# Sheet-circuit_de_puissance.net
KiCad netlist of a schematic drawn in Altium Designer
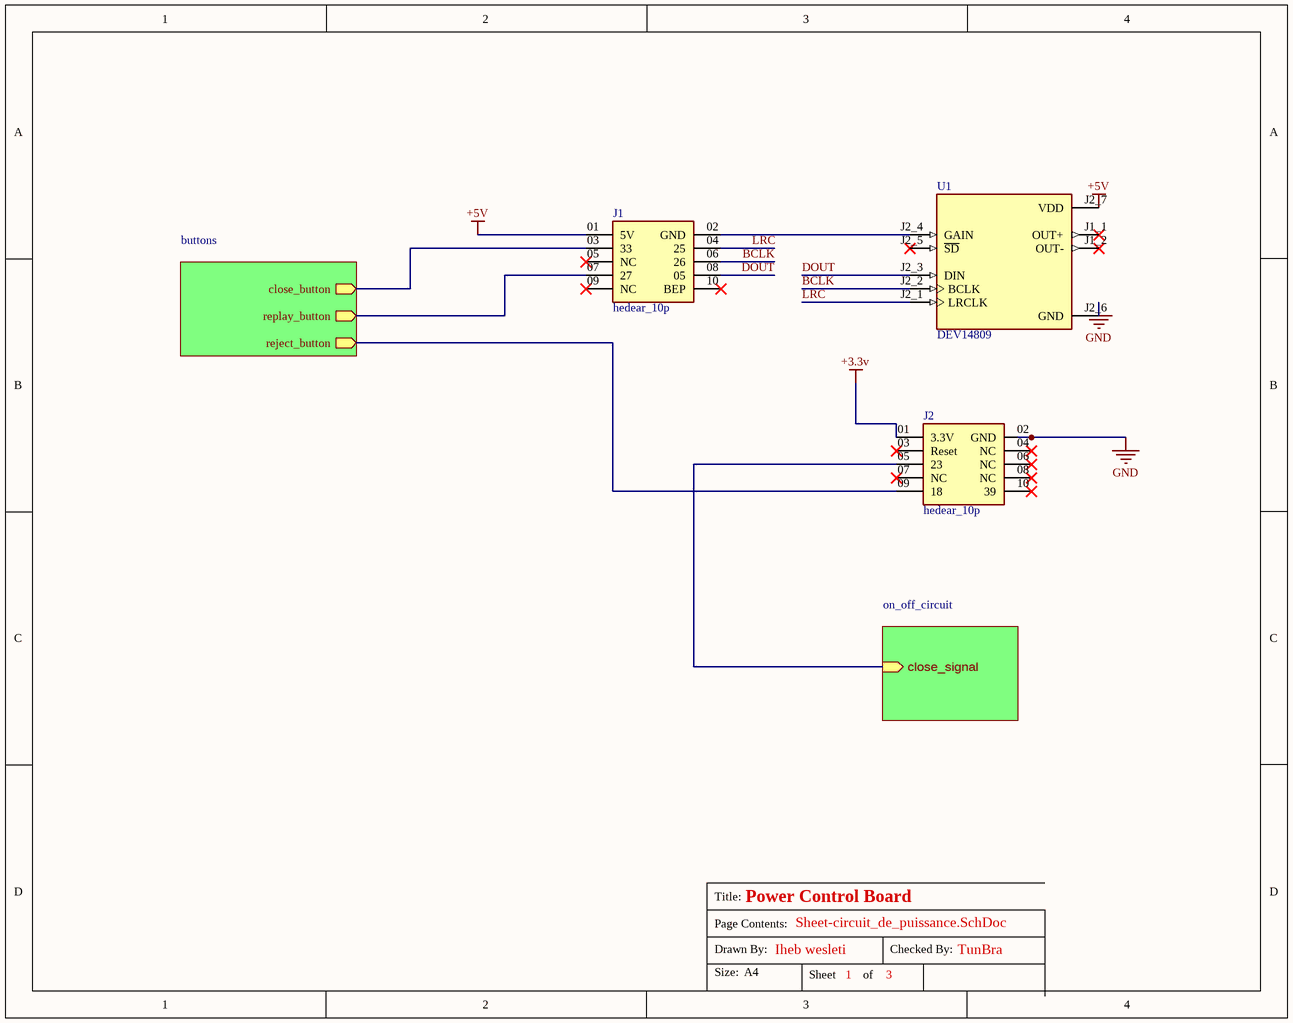
[diagram p0: Sheet-circuit_de_puissance.SchDoc]

(export (version "E")
  (design (tool "Eeschema 10.0.6"))
  (components
    (comp (ref "J1")
      (value "hedear_10p")
      (footprint "hedear10p")
      (fields (field (name "MP") "TSS-105-02-L-D"))
      (libsource (lib "Schlib_circuit_de_puissance") (part "hedear_10p"))
    )
    (comp (ref "J2")
      (value "hedear_10p")
      (footprint "hedear10p")
      (fields (field (name "MP") "TSS-105-02-L-D"))
      (libsource (lib "Schlib_circuit_de_puissance") (part "hedear_10p_1"))
    )
    (comp (ref "U1")
      (value "DEV14809")
      (footprint "MODULEson_DEV14809")
      (description "MAX98357A Audio Interface Audio - Platform Evaluation Expansion Board")
      (fields (field (name "MF") "Sparkfun Electronics"))
      (libsource (lib "Schlib_circuit_de_puissance") (part "DEV14809"))
    )
  )
  (nets
    (net (code "1") (name "+3.3v") (class "Default")
      (node (ref "J2") (pin "01") (pinfunction "3.3V_01") (pintype "passive"))
    )
    (net (code "2") (name "+5V") (class "Default")
      (node (ref "J1") (pin "01") (pinfunction "5V_01") (pintype "passive"))
      (node (ref "U1") (pin "J2_7") (pinfunction "VDD_J2_7") (pintype "power_in"))
    )
    (net (code "3") (name "/BCLK") (class "Default")
      (node (ref "J1") (pin "06") (pinfunction "26_06") (pintype "passive"))
      (node (ref "U1") (pin "J2_2") (pinfunction "BCLK_J2_2") (pintype "input"))
    )
    (net (code "4") (name "/DOUT") (class "Default")
      (node (ref "J1") (pin "08") (pinfunction "05_08") (pintype "passive"))
      (node (ref "U1") (pin "J2_3") (pinfunction "DIN_J2_3") (pintype "input"))
    )
    (net (code "5") (name "/LRC") (class "Default")
      (node (ref "J1") (pin "04") (pinfunction "25_04") (pintype "passive"))
      (node (ref "U1") (pin "J2_1") (pinfunction "LRCLK_J2_1") (pintype "input"))
    )
    (net (code "6") (name "/close_button") (class "Default")
      (node (ref "J1") (pin "03") (pinfunction "33_03") (pintype "passive"))
    )
    (net (code "7") (name "/close_signal") (class "Default")
      (node (ref "J2") (pin "05") (pinfunction "23_05") (pintype "passive"))
    )
    (net (code "8") (name "/reject_button") (class "Default")
      (node (ref "J2") (pin "09") (pinfunction "18_09") (pintype "passive"))
    )
    (net (code "9") (name "/replay_button") (class "Default")
      (node (ref "J1") (pin "07") (pinfunction "27_07") (pintype "passive"))
    )
    (net (code "10") (name "GND") (class "Default")
      (node (ref "J2") (pin "02") (pinfunction "GND_02") (pintype "passive"))
      (node (ref "U1") (pin "J2_6") (pinfunction "GND_J2_6") (pintype "power_in"))
    )
    (net (code "11") (name "Net-(J1-GND)") (class "Default")
      (node (ref "J1") (pin "02") (pinfunction "GND_02") (pintype "passive"))
      (node (ref "U1") (pin "J2_4") (pinfunction "GAIN_J2_4") (pintype "input"))
    )
    (net (code "12") (name "unconnected-(J1-BEP-Pad10)") (class "Default")
      (node (ref "J1") (pin "10") (pinfunction "BEP_10") (pintype "passive+no_connect"))
    )
    (net (code "13") (name "unconnected-(J1-NC-Pad05)") (class "Default")
      (node (ref "J1") (pin "05") (pinfunction "NC_05") (pintype "passive+no_connect"))
    )
    (net (code "14") (name "unconnected-(J1-NC-Pad09)") (class "Default")
      (node (ref "J1") (pin "09") (pinfunction "NC_09") (pintype "passive+no_connect"))
    )
    (net (code "15") (name "unconnected-(J2-39-Pad10)") (class "Default")
      (node (ref "J2") (pin "10") (pinfunction "39_10") (pintype "passive+no_connect"))
    )
    (net (code "16") (name "unconnected-(J2-NC-Pad04)") (class "Default")
      (node (ref "J2") (pin "04") (pinfunction "NC_04") (pintype "passive+no_connect"))
    )
    (net (code "17") (name "unconnected-(J2-NC-Pad06)") (class "Default")
      (node (ref "J2") (pin "06") (pinfunction "NC_06") (pintype "passive+no_connect"))
    )
    (net (code "18") (name "unconnected-(J2-NC-Pad07)") (class "Default")
      (node (ref "J2") (pin "07") (pinfunction "NC_07") (pintype "passive+no_connect"))
    )
    (net (code "19") (name "unconnected-(J2-NC-Pad08)") (class "Default")
      (node (ref "J2") (pin "08") (pinfunction "NC_08") (pintype "passive+no_connect"))
    )
    (net (code "20") (name "unconnected-(J2-Reset-Pad03)") (class "Default")
      (node (ref "J2") (pin "03") (pinfunction "Reset_03") (pintype "passive+no_connect"))
    )
    (net (code "21") (name "unconnected-(U1-OUT+-PadJ1_1)") (class "Default")
      (node (ref "U1") (pin "J1_1") (pinfunction "OUT+_J1_1") (pintype "output+no_connect"))
    )
    (net (code "22") (name "unconnected-(U1-OUT--PadJ1_2)") (class "Default")
      (node (ref "U1") (pin "J1_2") (pinfunction "OUT-_J1_2") (pintype "output+no_connect"))
    )
    (net (code "23") (name "unconnected-(U1-~{SD}-PadJ2_5)") (class "Default")
      (node (ref "U1") (pin "J2_5") (pinfunction "~{SD}_J2_5") (pintype "input+no_connect"))
    )
  )
)
